# 3V3_Isolation.net
KiCad netlist of a schematic drawn in Altium Designer
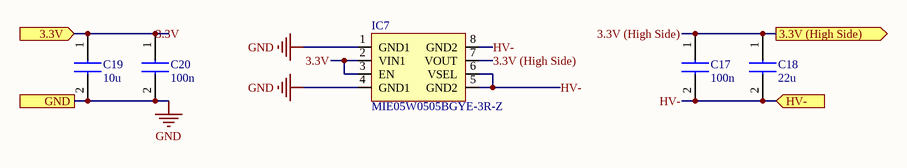
[diagram p0: 3V3_Isolation.SchDoc]

(export (version "E")
  (design (tool "Eeschema 10.0.6"))
  (components
    (comp (ref "C17")
      (value "100n")
      (footprint "SamacSys:CAPC3216X94N")
      (description "Capacitor")
      (fields
        (field (name "MANUFACTURER_PART_NUMBER") "12065C104J4Z2A")
        (field (name "MOUSER PART NUMBER") "581-12065C104J4Z2A")
      )
      (libsource (lib "SamacSys") (part "12065C104J4Z2A"))
    )
    (comp (ref "C18")
      (value "22u")
      (footprint "SamacSys:CAPC3216X180N")
      (description "Capacitor")
      (fields (field (name "MANUFACTURER_PART_NUMBER") "GGM31CD70J226KE02L"))
      (libsource (lib "*") (part "GGM31CD70J226KE02L"))
    )
    (comp (ref "C19")
      (value "10u")
      (footprint "SamacSys:CAPC3216X180N")
      (description "Capacitor")
      (fields (field (name "MANUFACTURER_PART_NUMBER") "MLASU31LBB5106KTNA01"))
      (libsource (lib "SamacSys") (part "MLASU31LBB5106KTNA01"))
    )
    (comp (ref "C20")
      (value "100n")
      (footprint "SamacSys:CAPC3216X94N")
      (description "Capacitor")
      (fields
        (field (name "MANUFACTURER_PART_NUMBER") "12065C104J4Z2A")
        (field (name "MOUSER PART NUMBER") "581-12065C104J4Z2A")
      )
      (libsource (lib "SamacSys") (part "12065C104J4Z2A"))
    )
    (comp (ref "IC7")
      (value "MIE05W0505BGYE-3R-Z")
      (footprint "SOIC127P1030X265-8N")
      (libsource (lib "SamacSys") (part "MIE05W0505BGYE-3R-Z"))
    )
  )
  (nets
    (net (code "1") (name "/3.3V") (class "Default")
      (node (ref "C19") (pin "1") (pinfunction "1_1") (pintype "passive"))
      (node (ref "C20") (pin "1") (pinfunction "1_1") (pintype "passive"))
      (node (ref "IC7") (pin "2") (pinfunction "VIN1_2") (pintype "passive"))
      (node (ref "IC7") (pin "3") (pinfunction "EN_3") (pintype "passive"))
    )
    (net (code "2") (name "/3.3V (High Side)") (class "Default")
      (node (ref "C17") (pin "1") (pinfunction "1_1") (pintype "passive"))
      (node (ref "C18") (pin "1") (pinfunction "1_1") (pintype "passive"))
      (node (ref "IC7") (pin "7") (pinfunction "VOUT_7") (pintype "passive"))
    )
    (net (code "3") (name "/HV-") (class "Default")
      (node (ref "C17") (pin "2") (pinfunction "2_2") (pintype "passive"))
      (node (ref "C18") (pin "2") (pinfunction "2_2") (pintype "passive"))
      (node (ref "IC7") (pin "5") (pinfunction "GND2_5") (pintype "passive"))
      (node (ref "IC7") (pin "6") (pinfunction "VSEL_6") (pintype "passive"))
      (node (ref "IC7") (pin "8") (pinfunction "GND2_8") (pintype "passive"))
    )
    (net (code "4") (name "GND") (class "Default")
      (node (ref "C19") (pin "2") (pinfunction "2_2") (pintype "passive"))
      (node (ref "C20") (pin "2") (pinfunction "2_2") (pintype "passive"))
      (node (ref "IC7") (pin "1") (pinfunction "GND1_1") (pintype "passive"))
      (node (ref "IC7") (pin "4") (pinfunction "GND1_4") (pintype "passive"))
    )
  )
)
